# ESP32-S3-STD2.net
KiCad netlist of a schematic drawn in Altium Designer
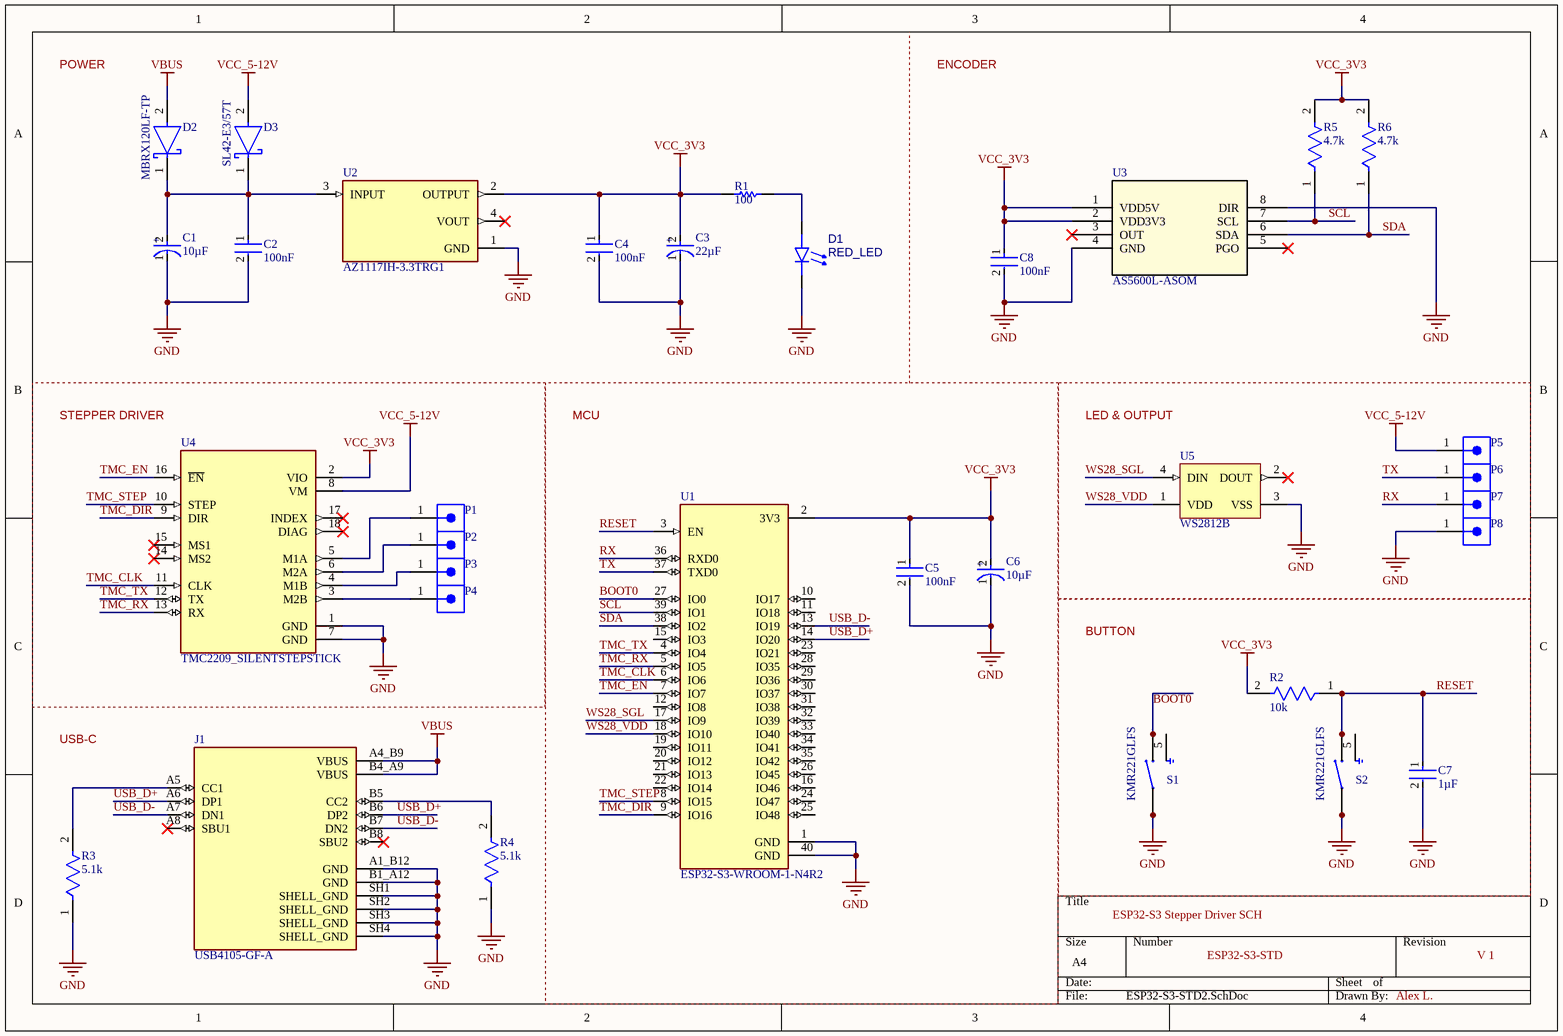
[diagram p0: ESP32-S3-STD2.SchDoc]

(export (version "E")
  (design (tool "Eeschema 10.0.6"))
  (components
    (comp (ref "C1")
      (value "10µF")
      (footprint "FP-FKB-MFG")
      (fields (field (name "Comment") "EEE-FK1C100R"))
      (libsource (lib "Cegep Edouard-Montpetit") (part "203bc49f2ac43e59fd269a8c329ed05"))
    )
    (comp (ref "C2")
      (value "100nF")
      (footprint "FP-C1206C-EB-MFG")
      (fields (field (name "Comment") "C1206C104K5RAC7210"))
      (libsource (lib "Cegep Edouard-Montpetit") (part "b4654b650e69147ec39a6b967a45e02"))
    )
    (comp (ref "C3")
      (value "22µF")
      (footprint "FP-FKC-MFG")
      (fields (field (name "Comment") "EEE-FK1V220R"))
      (libsource (lib "Cegep Edouard-Montpetit") (part "a00bbbee19879c290e62620ae7e47b1"))
    )
    (comp (ref "C4")
      (value "100nF")
      (footprint "FP-C1206C-EB-MFG")
      (fields (field (name "Comment") "C1206C104K5RAC7210"))
      (libsource (lib "Cegep Edouard-Montpetit") (part "b4654b650e69147ec39a6b967a45e02"))
    )
    (comp (ref "C5")
      (value "100nF")
      (footprint "FP-C1206C-EB-MFG")
      (fields (field (name "Comment") "C1206C104K5RAC7210"))
      (libsource (lib "Cegep Edouard-Montpetit") (part "b4654b650e69147ec39a6b967a45e02"))
    )
    (comp (ref "C6")
      (value "10µF")
      (footprint "FP-FKB-MFG")
      (fields (field (name "Comment") "EEE-FK1C100R"))
      (libsource (lib "Cegep Edouard-Montpetit") (part "203bc49f2ac43e59fd269a8c329ed05"))
    )
    (comp (ref "C7")
      (value "1µF")
      (footprint "FP-CL31-IPC_C")
      (fields (field (name "Comment") "CL31B105KOFNNNE"))
      (libsource (lib "Cegep Edouard-Montpetit") (part "b4654b650e69147ec39a6b967a45e02"))
    )
    (comp (ref "C8")
      (value "100nF")
      (footprint "FP-C1206C-EB-MFG")
      (fields (field (name "Comment") "C1206C104K5RAC7210"))
      (libsource (lib "Cegep Edouard-Montpetit") (part "b4654b650e69147ec39a6b967a45e02"))
    )
    (comp (ref "D1")
      (value "RED_LED")
      (footprint "LITE-ON-LTST-C191KRKT-2_V")
      (description "Single Color LED, Red, Water Clear, 1.1mm")
      (libsource (lib "Cegep Edouard-Montpetit") (part "DIODE-LED-2"))
    )
    (comp (ref "D2")
      (value "MBRX120LF-TP")
      (footprint "FP-SOD-123-IPC_B")
      (description "Rectifier Diode, Schottky, 1 Phase, 1 Element, 1A, 20V V(RRM), Silicon")
      (libsource (lib "Cegep Edouard-Montpetit") (part "1d6ec82d83fb6aee721767c19dac4b9"))
    )
    (comp (ref "D3")
      (value "SL42-E3/57T")
      (footprint "FP-95402-MFG")
      (description "Rectifier Diode, Schottky, 1 Phase, 1 Element, 4A, 20V V(RRM), Silicon, DO-214AB")
      (libsource (lib "Cegep Edouard-Montpetit") (part "c1678fac7984e62e0809fbf79c06691"))
    )
    (comp (ref "J1")
      (value "USB4105-GF-A")
      (footprint "GCT_USB4105-GF-A")
      (fields (field (name "MF") "GCT"))
      (libsource (lib "USB4105-GF-A") (part "USB4105-GF-A"))
    )
    (comp (ref "P1")
      (value "61300111121")
      (footprint "61300111121")
      (libsource (lib "Cegep Edouard-Montpetit") (part "Header_Male_1R_01P"))
    )
    (comp (ref "P2")
      (value "61300111121")
      (footprint "61300111121")
      (libsource (lib "Cegep Edouard-Montpetit") (part "Header_Male_1R_01P"))
    )
    (comp (ref "P3")
      (value "61300111121")
      (footprint "61300111121")
      (libsource (lib "Cegep Edouard-Montpetit") (part "Header_Male_1R_01P"))
    )
    (comp (ref "P4")
      (value "61300111121")
      (footprint "61300111121")
      (libsource (lib "Cegep Edouard-Montpetit") (part "Header_Male_1R_01P"))
    )
    (comp (ref "P5")
      (value "61300111121")
      (footprint "61300111121")
      (libsource (lib "Cegep Edouard-Montpetit") (part "Header_Male_1R_01P"))
    )
    (comp (ref "P6")
      (value "61300111121")
      (footprint "61300111121")
      (libsource (lib "Cegep Edouard-Montpetit") (part "Header_Male_1R_01P"))
    )
    (comp (ref "P7")
      (value "61300111121")
      (footprint "61300111121")
      (libsource (lib "Cegep Edouard-Montpetit") (part "Header_Male_1R_01P"))
    )
    (comp (ref "P8")
      (value "61300111121")
      (footprint "61300111121")
      (libsource (lib "Cegep Edouard-Montpetit") (part "Header_Male_1R_01P"))
    )
    (comp (ref "R1")
      (value "100")
      (footprint "RESC3216X70X50NL05T20")
      (fields
        (field (name "POWER") "250mW")
        (field (name "TOLERANCE") "1%")
        (field (name "Comment") "ERJ-8ENF1000V")
      )
      (libsource (lib "Cegep Edouard-Montpetit") (part "RES"))
    )
    (comp (ref "R2")
      (value "10k")
      (footprint "FP-RMCF1206-IPC_B")
      (fields
        (field (name "POWER") "250mW")
        (field (name "TOLERANCE") "1%")
        (field (name "Comment") "RMCF1206FT10K0")
      )
      (libsource (lib "Cegep Edouard-Montpetit") (part "1029c3af85768c4190bb7ad29bc67b5"))
    )
    (comp (ref "R3")
      (value "5.1k")
      (footprint "FP-RMCF1206-IPC_B")
      (fields
        (field (name "TOLERANCE") "5%")
        (field (name "POWER") "250mW")
        (field (name "Comment") "RMCF1206JT5K10")
      )
      (libsource (lib "Cegep Edouard-Montpetit") (part "1029c3af85768c4190bb7ad29bc67b5"))
    )
    (comp (ref "R4")
      (value "5.1k")
      (footprint "FP-RMCF1206-IPC_B")
      (fields
        (field (name "TOLERANCE") "5%")
        (field (name "POWER") "250mW")
        (field (name "Comment") "RMCF1206JT5K10")
      )
      (libsource (lib "Cegep Edouard-Montpetit") (part "1029c3af85768c4190bb7ad29bc67b5"))
    )
    (comp (ref "R5")
      (value "4.7k")
      (footprint "FP-RMCF1206-IPC_B")
      (fields
        (field (name "TOLERANCE") "5%")
        (field (name "POWER") "250mW")
        (field (name "Comment") "RMCF1206JT4K70")
      )
      (libsource (lib "Cegep Edouard-Montpetit") (part "1029c3af85768c4190bb7ad29bc67b5"))
    )
    (comp (ref "R6")
      (value "4.7k")
      (footprint "FP-RMCF1206-IPC_B")
      (fields
        (field (name "TOLERANCE") "5%")
        (field (name "POWER") "250mW")
        (field (name "Comment") "RMCF1206JT4K70")
      )
      (libsource (lib "Cegep Edouard-Montpetit") (part "1029c3af85768c4190bb7ad29bc67b5"))
    )
    (comp (ref "S1")
      (value "KMR221GLFS")
      (footprint "SW_KMR221GLFS")
      (description "Switch Tactile N.O. SPST Button Gull Wing 0.05A 32VDC 1VA 200000Cycles 2N SMD Automotive T/R")
      (libsource (lib "KMR221GLFS") (part "KMR221GLFS"))
    )
    (comp (ref "S2")
      (value "KMR221GLFS")
      (footprint "SW_KMR221GLFS")
      (description "Switch Tactile N.O. SPST Button Gull Wing 0.05A 32VDC 1VA 200000Cycles 2N SMD Automotive T/R")
      (libsource (lib "KMR221GLFS") (part "KMR221GLFS"))
    )
    (comp (ref "U1")
      (value "ESP32-S3-WROOM-1-N4R2")
      (footprint "XCVR_ESP32-S3-WROOM-1-N4R2")
      (description "Bluetooth, WiFi 802.11b/g/n, Bluetooth v5.0 Transceiver Module 2.4GHz PCB Trace Surface Mount")
      (fields (field (name "MF") "Espressif Systems"))
      (libsource (lib "ESP32-S3-WROOM-1-N4R2_2") (part "ESP32-S3-WROOM-1-N4R2"))
    )
    (comp (ref "U2")
      (value "AZ1117IH-3.3TRG1")
      (footprint "SOT230P700X185-4N")
      (description "Linear Voltage Regulator IC Positive Fixed 1 Output 1A SOT-223-3")
      (fields (field (name "MF") "Diodes Inc."))
      (libsource (lib "AZ1117IH-3.3TRG1") (part "AZ1117IH-3.3TRG1"))
    )
    (comp (ref "U3")
      (value "AS5600L-ASOM")
      (footprint "SOIC127P600X175-8N")
      (description "No Description Available")
      (fields (field (name "COPYRIGHT") "Copyright (C) 2023 Ultra Librarian. All rights reserved."))
      (libsource (lib "AS5600L-ASOM") (part "AS5600L-ASOM"))
    )
    (comp (ref "U4")
      (value "TMC2209_SILENTSTEPSTICK")
      (footprint "MODULE_TMC2209_SILENTSTEPSTICK")
      (description "TMC2209 Motor Controller/Driver Power Management Evaluation Board")
      (fields
        (field (name "MP") "TMC2209 SILENTSTEPSTICK")
        (field (name "MF") "Trinamic Motion Control GmbH")
      )
      (libsource (lib "TMC2209_SILENTSTEPSTICK") (part "TMC2209_SILENTSTEPSTICK"))
    )
    (comp (ref "U5")
      (value "WS2812B")
      (footprint "ADA-RGB-1655_V")
      (description "WS2812B 5050 RGB LED WITH INTEGRATED DRIVER CHIP PACK OF 10")
      (libsource (lib "Cegep Edouard-Montpetit") (part "ADA-RGB-1655-4"))
    )
  )
  (nets
    (net (code "1") (name "/BOOT0") (class "Default")
      (node (ref "S1") (pin "2") (pinfunction "3_2") (pintype "passive"))
      (node (ref "S1") (pin "3") (pinfunction "3_3") (pintype "passive"))
      (node (ref "U1") (pin "27") (pinfunction "IO0_27") (pintype "bidirectional"))
    )
    (net (code "2") (name "/RESET") (class "Default")
      (node (ref "C7") (pin "1") (pinfunction "1_1") (pintype "passive"))
      (node (ref "R2") (pin "1") (pinfunction "1_1") (pintype "passive"))
      (node (ref "S2") (pin "2") (pinfunction "3_2") (pintype "passive"))
      (node (ref "S2") (pin "3") (pinfunction "3_3") (pintype "passive"))
      (node (ref "U1") (pin "3") (pinfunction "EN_3") (pintype "input"))
    )
    (net (code "3") (name "/RX") (class "Default")
      (node (ref "P7") (pin "1") (pinfunction "1_1") (pintype "passive"))
      (node (ref "U1") (pin "36") (pinfunction "RXD0_36") (pintype "bidirectional"))
    )
    (net (code "4") (name "/SCL") (class "Default")
      (node (ref "R5") (pin "1") (pinfunction "1_1") (pintype "passive"))
      (node (ref "U1") (pin "39") (pinfunction "IO1_39") (pintype "bidirectional"))
      (node (ref "U3") (pin "7") (pinfunction "SCL_7") (pintype "passive"))
    )
    (net (code "5") (name "/SDA") (class "Default")
      (node (ref "R6") (pin "1") (pinfunction "1_1") (pintype "passive"))
      (node (ref "U1") (pin "38") (pinfunction "IO2_38") (pintype "bidirectional"))
      (node (ref "U3") (pin "6") (pinfunction "SDA_6") (pintype "passive"))
    )
    (net (code "6") (name "/TMC_CLK") (class "Default")
      (node (ref "U1") (pin "6") (pinfunction "IO6_6") (pintype "bidirectional"))
      (node (ref "U4") (pin "11") (pinfunction "CLK_11") (pintype "input"))
    )
    (net (code "7") (name "/TMC_DIR") (class "Default")
      (node (ref "U1") (pin "9") (pinfunction "IO16_9") (pintype "bidirectional"))
      (node (ref "U4") (pin "9") (pinfunction "DIR_9") (pintype "input"))
    )
    (net (code "8") (name "/TMC_EN") (class "Default")
      (node (ref "U1") (pin "7") (pinfunction "IO7_7") (pintype "bidirectional"))
      (node (ref "U4") (pin "16") (pinfunction "~{EN}_16") (pintype "input"))
    )
    (net (code "9") (name "/TMC_RX") (class "Default")
      (node (ref "U1") (pin "5") (pinfunction "IO5_5") (pintype "bidirectional"))
      (node (ref "U4") (pin "13") (pinfunction "RX_13") (pintype "bidirectional"))
    )
    (net (code "10") (name "/TMC_STEP") (class "Default")
      (node (ref "U1") (pin "8") (pinfunction "IO15_8") (pintype "bidirectional"))
      (node (ref "U4") (pin "10") (pinfunction "STEP_10") (pintype "input"))
    )
    (net (code "11") (name "/TMC_TX") (class "Default")
      (node (ref "U1") (pin "4") (pinfunction "IO4_4") (pintype "bidirectional"))
      (node (ref "U4") (pin "12") (pinfunction "TX_12") (pintype "bidirectional"))
    )
    (net (code "12") (name "/TX") (class "Default")
      (node (ref "P6") (pin "1") (pinfunction "1_1") (pintype "passive"))
      (node (ref "U1") (pin "37") (pinfunction "TXD0_37") (pintype "bidirectional"))
    )
    (net (code "13") (name "/USB_D+") (class "Default")
      (node (ref "J1") (pin "A6") (pinfunction "DP1_A6") (pintype "bidirectional"))
      (node (ref "J1") (pin "B6") (pinfunction "DP2_B6") (pintype "bidirectional"))
      (node (ref "U1") (pin "14") (pinfunction "IO20_14") (pintype "bidirectional"))
    )
    (net (code "14") (name "/USB_D-") (class "Default")
      (node (ref "J1") (pin "A7") (pinfunction "DN1_A7") (pintype "bidirectional"))
      (node (ref "J1") (pin "B7") (pinfunction "DN2_B7") (pintype "bidirectional"))
      (node (ref "U1") (pin "13") (pinfunction "IO19_13") (pintype "bidirectional"))
    )
    (net (code "15") (name "/WS28_SGL") (class "Default")
      (node (ref "U1") (pin "17") (pinfunction "IO9_17") (pintype "bidirectional"))
      (node (ref "U5") (pin "4") (pinfunction "DIN_4") (pintype "input"))
    )
    (net (code "16") (name "/WS28_VDD") (class "Default")
      (node (ref "U1") (pin "18") (pinfunction "IO10_18") (pintype "bidirectional"))
      (node (ref "U5") (pin "1") (pinfunction "VDD_1") (pintype "power_in"))
    )
    (net (code "17") (name "GND") (class "Default")
      (node (ref "C1") (pin "1") (pinfunction "C_1") (pintype "passive"))
      (node (ref "C2") (pin "2") (pinfunction "2_2") (pintype "passive"))
      (node (ref "C3") (pin "1") (pinfunction "C_1") (pintype "passive"))
      (node (ref "C4") (pin "2") (pinfunction "2_2") (pintype "passive"))
      (node (ref "C5") (pin "2") (pinfunction "2_2") (pintype "passive"))
      (node (ref "C6") (pin "1") (pinfunction "C_1") (pintype "passive"))
      (node (ref "C7") (pin "2") (pinfunction "2_2") (pintype "passive"))
      (node (ref "C8") (pin "2") (pinfunction "2_2") (pintype "passive"))
      (node (ref "D1") (pin "1") (pinfunction "K_1") (pintype "passive"))
      (node (ref "J1") (pin "A1_B12") (pinfunction "GND_A1_B12") (pintype "power_in"))
      (node (ref "J1") (pin "B1_A12") (pinfunction "GND_B1_A12") (pintype "power_in"))
      (node (ref "J1") (pin "SH1") (pinfunction "SHELL_GND_SH1") (pintype "power_in"))
      (node (ref "J1") (pin "SH2") (pinfunction "SHELL_GND_SH2") (pintype "power_in"))
      (node (ref "J1") (pin "SH3") (pinfunction "SHELL_GND_SH3") (pintype "power_in"))
      (node (ref "J1") (pin "SH4") (pinfunction "SHELL_GND_SH4") (pintype "power_in"))
      (node (ref "P8") (pin "1") (pinfunction "1_1") (pintype "passive"))
      (node (ref "R3") (pin "1") (pinfunction "1_1") (pintype "passive"))
      (node (ref "R4") (pin "1") (pinfunction "1_1") (pintype "passive"))
      (node (ref "S1") (pin "1") (pinfunction "1_1") (pintype "passive"))
      (node (ref "S1") (pin "4") (pinfunction "1_4") (pintype "passive"))
      (node (ref "S2") (pin "1") (pinfunction "1_1") (pintype "passive"))
      (node (ref "S2") (pin "4") (pinfunction "1_4") (pintype "passive"))
      (node (ref "U1") (pin "1") (pinfunction "GND_1") (pintype "power_in"))
      (node (ref "U1") (pin "40") (pinfunction "GND_40") (pintype "power_in"))
      (node (ref "U2") (pin "1") (pinfunction "GND_1") (pintype "power_in"))
      (node (ref "U3") (pin "4") (pinfunction "GND_4") (pintype "passive"))
      (node (ref "U3") (pin "8") (pinfunction "DIR_8") (pintype "passive"))
      (node (ref "U4") (pin "1") (pinfunction "GND_1") (pintype "power_in"))
      (node (ref "U4") (pin "7") (pinfunction "GND_7") (pintype "power_in"))
      (node (ref "U5") (pin "3") (pinfunction "VSS_3") (pintype "power_in"))
    )
    (net (code "18") (name "Net-(C1-A)") (class "Default")
      (node (ref "C1") (pin "2") (pinfunction "A_2") (pintype "passive"))
      (node (ref "C2") (pin "1") (pinfunction "1_1") (pintype "passive"))
      (node (ref "D2") (pin "1") (pinfunction "C_1") (pintype "passive"))
      (node (ref "D3") (pin "1") (pinfunction "C_1") (pintype "passive"))
      (node (ref "U2") (pin "3") (pinfunction "INPUT_3") (pintype "input"))
    )
    (net (code "19") (name "Net-(D1-A)") (class "Default")
      (node (ref "D1") (pin "2") (pinfunction "A_2") (pintype "passive"))
      (node (ref "R1") (pin "2") (pinfunction "2_2") (pintype "passive"))
    )
    (net (code "20") (name "Net-(J1-CC1)") (class "Default")
      (node (ref "J1") (pin "A5") (pinfunction "CC1_A5") (pintype "bidirectional"))
      (node (ref "R3") (pin "2") (pinfunction "2_2") (pintype "passive"))
    )
    (net (code "21") (name "Net-(J1-CC2)") (class "Default")
      (node (ref "J1") (pin "B5") (pinfunction "CC2_B5") (pintype "bidirectional"))
      (node (ref "R4") (pin "2") (pinfunction "2_2") (pintype "passive"))
    )
    (net (code "22") (name "Net-(U4-M1A)") (class "Default")
      (node (ref "P1") (pin "1") (pinfunction "1_1") (pintype "passive"))
      (node (ref "U4") (pin "5") (pinfunction "M1A_5") (pintype "output"))
    )
    (net (code "23") (name "Net-(U4-M1B)") (class "Default")
      (node (ref "P3") (pin "1") (pinfunction "1_1") (pintype "passive"))
      (node (ref "U4") (pin "4") (pinfunction "M1B_4") (pintype "output"))
    )
    (net (code "24") (name "Net-(U4-M2A)") (class "Default")
      (node (ref "P2") (pin "1") (pinfunction "1_1") (pintype "passive"))
      (node (ref "U4") (pin "6") (pinfunction "M2A_6") (pintype "output"))
    )
    (net (code "25") (name "Net-(U4-M2B)") (class "Default")
      (node (ref "P4") (pin "1") (pinfunction "1_1") (pintype "passive"))
      (node (ref "U4") (pin "3") (pinfunction "M2B_3") (pintype "output"))
    )
    (net (code "26") (name "VBUS") (class "Default")
      (node (ref "D2") (pin "2") (pinfunction "A_2") (pintype "passive"))
      (node (ref "J1") (pin "A4_B9") (pinfunction "VBUS_A4_B9") (pintype "power_in"))
      (node (ref "J1") (pin "B4_A9") (pinfunction "VBUS_B4_A9") (pintype "power_in"))
    )
    (net (code "27") (name "VCC_3V3") (class "Default")
      (node (ref "C3") (pin "2") (pinfunction "A_2") (pintype "passive"))
      (node (ref "C4") (pin "1") (pinfunction "1_1") (pintype "passive"))
      (node (ref "C5") (pin "1") (pinfunction "1_1") (pintype "passive"))
      (node (ref "C6") (pin "2") (pinfunction "A_2") (pintype "passive"))
      (node (ref "C8") (pin "1") (pinfunction "1_1") (pintype "passive"))
      (node (ref "R1") (pin "1") (pinfunction "1_1") (pintype "passive"))
      (node (ref "R2") (pin "2") (pinfunction "2_2") (pintype "passive"))
      (node (ref "R5") (pin "2") (pinfunction "2_2") (pintype "passive"))
      (node (ref "R6") (pin "2") (pinfunction "2_2") (pintype "passive"))
      (node (ref "U1") (pin "2") (pinfunction "3V3_2") (pintype "power_in"))
      (node (ref "U2") (pin "2") (pinfunction "OUTPUT_2") (pintype "output"))
      (node (ref "U3") (pin "1") (pinfunction "VDD5V_1") (pintype "passive"))
      (node (ref "U3") (pin "2") (pinfunction "VDD3V3_2") (pintype "passive"))
      (node (ref "U4") (pin "2") (pinfunction "VIO_2") (pintype "power_in"))
    )
    (net (code "28") (name "VCC_5-12V") (class "Default")
      (node (ref "D3") (pin "2") (pinfunction "A_2") (pintype "passive"))
      (node (ref "P5") (pin "1") (pinfunction "1_1") (pintype "passive"))
      (node (ref "U4") (pin "8") (pinfunction "VM_8") (pintype "power_in"))
    )
    (net (code "29") (name "unconnected-(J1-SBU1-PadA8)") (class "Default")
      (node (ref "J1") (pin "A8") (pinfunction "SBU1_A8") (pintype "bidirectional+no_connect"))
    )
    (net (code "30") (name "unconnected-(J1-SBU2-PadB8)") (class "Default")
      (node (ref "J1") (pin "B8") (pinfunction "SBU2_B8") (pintype "bidirectional+no_connect"))
    )
    (net (code "31") (name "unconnected-(S1-Pad5)") (class "Default")
      (node (ref "S1") (pin "5") (pinfunction "5_5") (pintype "passive"))
    )
    (net (code "32") (name "unconnected-(S2-Pad5)") (class "Default")
      (node (ref "S2") (pin "5") (pinfunction "5_5") (pintype "passive"))
    )
    (net (code "33") (name "unconnected-(U1-IO3-Pad15)") (class "Default")
      (node (ref "U1") (pin "15") (pinfunction "IO3_15") (pintype "bidirectional"))
    )
    (net (code "34") (name "unconnected-(U1-IO8-Pad12)") (class "Default")
      (node (ref "U1") (pin "12") (pinfunction "IO8_12") (pintype "bidirectional"))
    )
    (net (code "35") (name "unconnected-(U1-IO11-Pad19)") (class "Default")
      (node (ref "U1") (pin "19") (pinfunction "IO11_19") (pintype "bidirectional"))
    )
    (net (code "36") (name "unconnected-(U1-IO12-Pad20)") (class "Default")
      (node (ref "U1") (pin "20") (pinfunction "IO12_20") (pintype "bidirectional"))
    )
    (net (code "37") (name "unconnected-(U1-IO13-Pad21)") (class "Default")
      (node (ref "U1") (pin "21") (pinfunction "IO13_21") (pintype "bidirectional"))
    )
    (net (code "38") (name "unconnected-(U1-IO14-Pad22)") (class "Default")
      (node (ref "U1") (pin "22") (pinfunction "IO14_22") (pintype "bidirectional"))
    )
    (net (code "39") (name "unconnected-(U1-IO17-Pad10)") (class "Default")
      (node (ref "U1") (pin "10") (pinfunction "IO17_10") (pintype "bidirectional"))
    )
    (net (code "40") (name "unconnected-(U1-IO18-Pad11)") (class "Default")
      (node (ref "U1") (pin "11") (pinfunction "IO18_11") (pintype "bidirectional"))
    )
    (net (code "41") (name "unconnected-(U1-IO21-Pad23)") (class "Default")
      (node (ref "U1") (pin "23") (pinfunction "IO21_23") (pintype "bidirectional"))
    )
    (net (code "42") (name "unconnected-(U1-IO35-Pad28)") (class "Default")
      (node (ref "U1") (pin "28") (pinfunction "IO35_28") (pintype "bidirectional"))
    )
    (net (code "43") (name "unconnected-(U1-IO36-Pad29)") (class "Default")
      (node (ref "U1") (pin "29") (pinfunction "IO36_29") (pintype "bidirectional"))
    )
    (net (code "44") (name "unconnected-(U1-IO37-Pad30)") (class "Default")
      (node (ref "U1") (pin "30") (pinfunction "IO37_30") (pintype "bidirectional"))
    )
    (net (code "45") (name "unconnected-(U1-IO38-Pad31)") (class "Default")
      (node (ref "U1") (pin "31") (pinfunction "IO38_31") (pintype "bidirectional"))
    )
    (net (code "46") (name "unconnected-(U1-IO39-Pad32)") (class "Default")
      (node (ref "U1") (pin "32") (pinfunction "IO39_32") (pintype "bidirectional"))
    )
    (net (code "47") (name "unconnected-(U1-IO40-Pad33)") (class "Default")
      (node (ref "U1") (pin "33") (pinfunction "IO40_33") (pintype "bidirectional"))
    )
    (net (code "48") (name "unconnected-(U1-IO41-Pad34)") (class "Default")
      (node (ref "U1") (pin "34") (pinfunction "IO41_34") (pintype "bidirectional"))
    )
    (net (code "49") (name "unconnected-(U1-IO42-Pad35)") (class "Default")
      (node (ref "U1") (pin "35") (pinfunction "IO42_35") (pintype "bidirectional"))
    )
    (net (code "50") (name "unconnected-(U1-IO45-Pad26)") (class "Default")
      (node (ref "U1") (pin "26") (pinfunction "IO45_26") (pintype "bidirectional"))
    )
    (net (code "51") (name "unconnected-(U1-IO46-Pad16)") (class "Default")
      (node (ref "U1") (pin "16") (pinfunction "IO46_16") (pintype "bidirectional"))
    )
    (net (code "52") (name "unconnected-(U1-IO47-Pad24)") (class "Default")
      (node (ref "U1") (pin "24") (pinfunction "IO47_24") (pintype "bidirectional"))
    )
    (net (code "53") (name "unconnected-(U1-IO48-Pad25)") (class "Default")
      (node (ref "U1") (pin "25") (pinfunction "IO48_25") (pintype "bidirectional"))
    )
    (net (code "54") (name "unconnected-(U2-VOUT-Pad4)") (class "Default")
      (node (ref "U2") (pin "4") (pinfunction "VOUT_4") (pintype "output+no_connect"))
    )
    (net (code "55") (name "unconnected-(U3-OUT-Pad3)") (class "Default")
      (node (ref "U3") (pin "3") (pinfunction "OUT_3") (pintype "passive+no_connect"))
    )
    (net (code "56") (name "unconnected-(U3-PGO-Pad5)") (class "Default")
      (node (ref "U3") (pin "5") (pinfunction "PGO_5") (pintype "passive+no_connect"))
    )
    (net (code "57") (name "unconnected-(U4-DIAG-Pad18)") (class "Default")
      (node (ref "U4") (pin "18") (pinfunction "DIAG_18") (pintype "output+no_connect"))
    )
    (net (code "58") (name "unconnected-(U4-INDEX-Pad17)") (class "Default")
      (node (ref "U4") (pin "17") (pinfunction "INDEX_17") (pintype "output+no_connect"))
    )
    (net (code "59") (name "unconnected-(U4-MS1-Pad15)") (class "Default")
      (node (ref "U4") (pin "15") (pinfunction "MS1_15") (pintype "input+no_connect"))
    )
    (net (code "60") (name "unconnected-(U4-MS2-Pad14)") (class "Default")
      (node (ref "U4") (pin "14") (pinfunction "MS2_14") (pintype "input+no_connect"))
    )
    (net (code "61") (name "unconnected-(U5-DOUT-Pad2)") (class "Default")
      (node (ref "U5") (pin "2") (pinfunction "DOUT_2") (pintype "output+no_connect"))
    )
  )
)
